# Power_Supply.net
KiCad netlist of a schematic drawn in Altium Designer
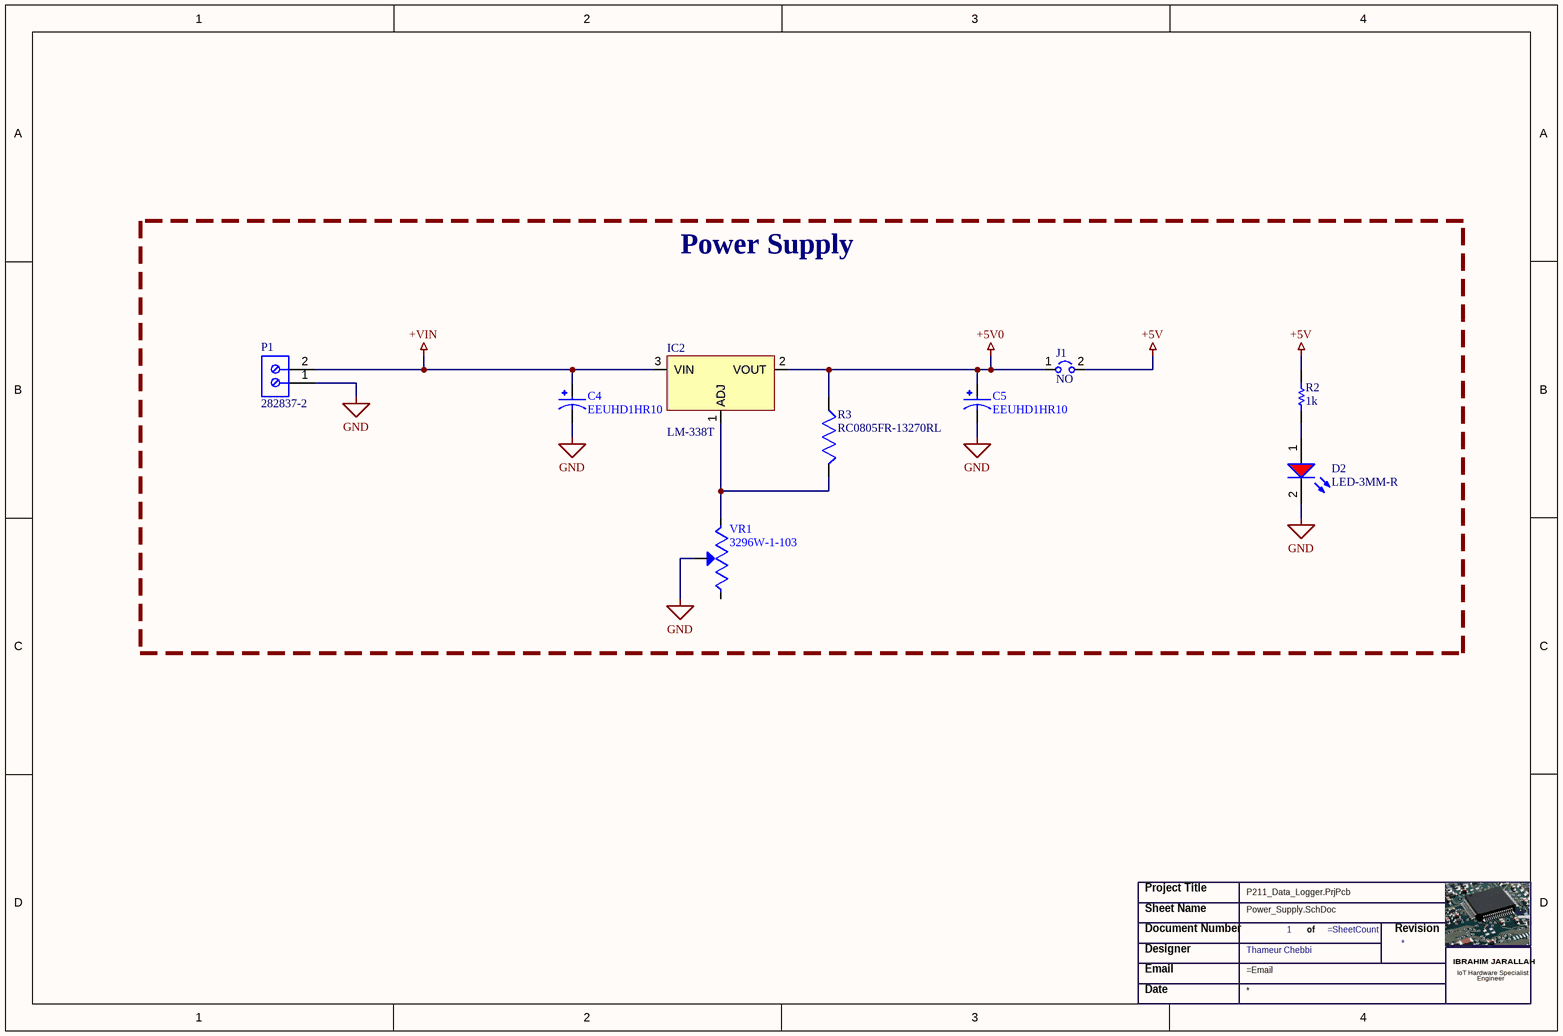
[diagram p0: Power_Supply.SchDoc]

(export (version "E")
  (design (tool "Eeschema 10.0.6"))
  (components
    (comp (ref "C4")
      (value "EEUHD1HR10")
      (footprint "CAP_ALUM_5x11_RM2.5")
      (fields (field (name "MF") "{'manufacturer': u'Panasonic'}"))
      (libsource (lib "EEU-HD1HR10") (part "EEUHD1HR10"))
    )
    (comp (ref "C5")
      (value "EEUHD1HR10")
      (footprint "CAP_ALUM_5x11_RM2.5")
      (fields (field (name "MF") "{'manufacturer': u'Panasonic'}"))
      (libsource (lib "EEU-HD1HR10") (part "EEUHD1HR10"))
    )
    (comp (ref "D2")
      (value "LED-3MM-R")
      (footprint "LED-2.54MM-R")
      (libsource (lib "SCH_THA") (part "LED-3MM-R"))
    )
    (comp (ref "IC2")
      (value "LM-338T")
      (footprint "TO-220-3")
      (libsource (lib "Symbol_Lib") (part "IC_LM_338T"))
    )
    (comp (ref "J1") (value "NO") (footprint "Jumper") (libsource (lib "Symbol_Lib") (part "Jumper_NO")))
    (comp (ref "P1")
      (value "282837-2")
      (footprint "TE_282837-2")
      (description "TERM BLOCK 5.08MM 2POS SIDE ENTY")
      (fields (field (name "MF") "{'manufacturer': u'TE Connectivity'}"))
      (libsource (lib "282837-2") (part "282837-2"))
    )
    (comp (ref "R2")
      (value "1k")
      (footprint "RESC2013X50X30LL20T20")
      (libsource (lib "SCH_THA") (part "RES-0805-SMD"))
    )
    (comp (ref "R3")
      (value "RC0805FR-13270RL")
      (footprint "RESC2012X60N")
      (fields (field (name "MF") "{'manufacturer': u'Yageo Corporation'}"))
      (libsource (lib "RC0805FR13270RL") (part "RC0805FR-13270RL"))
    )
    (comp (ref "VR1")
      (value "3296W-1-103")
      (footprint "TRIM_3296W-1-103")
      (fields (field (name "MF") "{'manufacturer': u'Bourns'}"))
      (libsource (lib "3296W-1-103") (part "3296W-1-103"))
    )
  )
  (nets
    (net (code "1") (name "+5V") (class "Default")
      (node (ref "J1") (pin "2") (pinfunction "2_2") (pintype "passive"))
      (node (ref "R2") (pin "1") (pinfunction "1_1") (pintype "passive"))
    )
    (net (code "2") (name "+5V0") (class "Default")
      (node (ref "C5") (pin "1") (pinfunction "P_1") (pintype "passive"))
      (node (ref "IC2") (pin "2") (pinfunction "VOUT_2") (pintype "passive"))
      (node (ref "J1") (pin "1") (pinfunction "1_1") (pintype "passive"))
      (node (ref "R3") (pin "2") (pinfunction "2_2") (pintype "passive"))
    )
    (net (code "3") (name "+VIN") (class "Default")
      (node (ref "C4") (pin "1") (pinfunction "P_1") (pintype "passive"))
      (node (ref "IC2") (pin "3") (pinfunction "VIN_3") (pintype "passive"))
      (node (ref "P1") (pin "2") (pinfunction "2_2") (pintype "passive"))
    )
    (net (code "4") (name "GND") (class "Default")
      (node (ref "C4") (pin "2") (pinfunction "N_2") (pintype "passive"))
      (node (ref "C5") (pin "2") (pinfunction "N_2") (pintype "passive"))
      (node (ref "D2") (pin "2") (pinfunction "K_2") (pintype "passive"))
      (node (ref "P1") (pin "1") (pinfunction "1_1") (pintype "passive"))
      (node (ref "VR1") (pin "2") (pinfunction "WIPER_2") (pintype "passive"))
    )
    (net (code "5") (name "Net-(D2-A)") (class "Default")
      (node (ref "D2") (pin "1") (pinfunction "A_1") (pintype "passive"))
      (node (ref "R2") (pin "2") (pinfunction "2_2") (pintype "passive"))
    )
    (net (code "6") (name "Net-(IC2-ADJ)") (class "Default")
      (node (ref "IC2") (pin "1") (pinfunction "ADJ_1") (pintype "passive"))
      (node (ref "R3") (pin "1") (pinfunction "1_1") (pintype "passive"))
      (node (ref "VR1") (pin "3") (pinfunction "CW_3") (pintype "passive"))
    )
    (net (code "7") (name "unconnected-(VR1-CCW-Pad1)") (class "Default")
      (node (ref "VR1") (pin "1") (pinfunction "CCW_1") (pintype "passive"))
    )
  )
)
